# ADE_short.net
KiCad netlist of a schematic drawn in Altium Designer
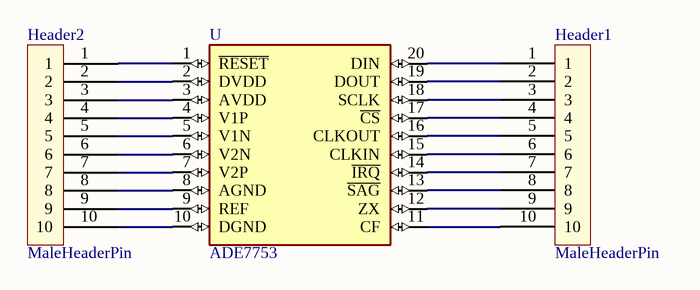
[diagram p0: ADE_short.SchDoc]

(export (version "E")
  (design (tool "Eeschema 10.0.6"))
  (components
    (comp (ref "Header1")
      (value "MaleHeaderPin")
      (footprint "Headerx10")
      (libsource (lib "Schlib1") (part "MaleHeaderPin"))
    )
    (comp (ref "Header2")
      (value "MaleHeaderPin")
      (footprint "Headerx10")
      (libsource (lib "") (part "MaleHeaderPin_1"))
    )
    (comp (ref "U")
      (value "ADE7753")
      (footprint "SSOP-20")
      (description "IC ENERGY METERING 1PHASE 20SSOP")
      (fields (field (name "DIGI-KEY_PART_NUMBER") "ADE7753ARSZRLCT-ND") (field (name "MF") "Analog Devices"))
      (libsource (lib "ADE7753") (part "ADE7753"))
    )
  )
  (nets
    (net (code "1") (name "Net-(U-AGND)") (class "Default")
      (node (ref "Header2") (pin "8") (pinfunction "8_8") (pintype "passive"))
      (node (ref "U") (pin "8") (pinfunction "AGND_8") (pintype "bidirectional"))
    )
    (net (code "2") (name "Net-(U-AVDD)") (class "Default")
      (node (ref "Header2") (pin "3") (pinfunction "3_3") (pintype "passive"))
      (node (ref "U") (pin "3") (pinfunction "AVDD_3") (pintype "bidirectional"))
    )
    (net (code "3") (name "Net-(U-CF)") (class "Default")
      (node (ref "Header1") (pin "10") (pinfunction "10_10") (pintype "passive"))
      (node (ref "U") (pin "11") (pinfunction "CF_11") (pintype "bidirectional"))
    )
    (net (code "4") (name "Net-(U-CLKIN)") (class "Default")
      (node (ref "Header1") (pin "6") (pinfunction "6_6") (pintype "passive"))
      (node (ref "U") (pin "15") (pinfunction "CLKIN_15") (pintype "bidirectional"))
    )
    (net (code "5") (name "Net-(U-CLKOUT)") (class "Default")
      (node (ref "Header1") (pin "5") (pinfunction "5_5") (pintype "passive"))
      (node (ref "U") (pin "16") (pinfunction "CLKOUT_16") (pintype "bidirectional"))
    )
    (net (code "6") (name "Net-(U-DGND)") (class "Default")
      (node (ref "Header2") (pin "10") (pinfunction "10_10") (pintype "passive"))
      (node (ref "U") (pin "10") (pinfunction "DGND_10") (pintype "bidirectional"))
    )
    (net (code "7") (name "Net-(U-DIN)") (class "Default")
      (node (ref "Header1") (pin "1") (pinfunction "1_1") (pintype "passive"))
      (node (ref "U") (pin "20") (pinfunction "DIN_20") (pintype "bidirectional"))
    )
    (net (code "8") (name "Net-(U-DOUT)") (class "Default")
      (node (ref "Header1") (pin "2") (pinfunction "2_2") (pintype "passive"))
      (node (ref "U") (pin "19") (pinfunction "DOUT_19") (pintype "bidirectional"))
    )
    (net (code "9") (name "Net-(U-DVDD)") (class "Default")
      (node (ref "Header2") (pin "2") (pinfunction "2_2") (pintype "passive"))
      (node (ref "U") (pin "2") (pinfunction "DVDD_2") (pintype "bidirectional"))
    )
    (net (code "10") (name "Net-(U-REF)") (class "Default")
      (node (ref "Header2") (pin "9") (pinfunction "9_9") (pintype "passive"))
      (node (ref "U") (pin "9") (pinfunction "REF_9") (pintype "bidirectional"))
    )
    (net (code "11") (name "Net-(U-SCLK)") (class "Default")
      (node (ref "Header1") (pin "3") (pinfunction "3_3") (pintype "passive"))
      (node (ref "U") (pin "18") (pinfunction "SCLK_18") (pintype "bidirectional"))
    )
    (net (code "12") (name "Net-(U-V1N)") (class "Default")
      (node (ref "Header2") (pin "5") (pinfunction "5_5") (pintype "passive"))
      (node (ref "U") (pin "5") (pinfunction "V1N_5") (pintype "bidirectional"))
    )
    (net (code "13") (name "Net-(U-V1P)") (class "Default")
      (node (ref "Header2") (pin "4") (pinfunction "4_4") (pintype "passive"))
      (node (ref "U") (pin "4") (pinfunction "V1P_4") (pintype "bidirectional"))
    )
    (net (code "14") (name "Net-(U-V2N)") (class "Default")
      (node (ref "Header2") (pin "6") (pinfunction "6_6") (pintype "passive"))
      (node (ref "U") (pin "6") (pinfunction "V2N_6") (pintype "bidirectional"))
    )
    (net (code "15") (name "Net-(U-V2P)") (class "Default")
      (node (ref "Header2") (pin "7") (pinfunction "7_7") (pintype "passive"))
      (node (ref "U") (pin "7") (pinfunction "V2P_7") (pintype "bidirectional"))
    )
    (net (code "16") (name "Net-(U-ZX)") (class "Default")
      (node (ref "Header1") (pin "9") (pinfunction "9_9") (pintype "passive"))
      (node (ref "U") (pin "12") (pinfunction "ZX_12") (pintype "bidirectional"))
    )
    (net (code "17") (name "Net-(U-~{CS})") (class "Default")
      (node (ref "Header1") (pin "4") (pinfunction "4_4") (pintype "passive"))
      (node (ref "U") (pin "17") (pinfunction "~{CS}_17") (pintype "bidirectional"))
    )
    (net (code "18") (name "Net-(U-~{IRQ})") (class "Default")
      (node (ref "Header1") (pin "7") (pinfunction "7_7") (pintype "passive"))
      (node (ref "U") (pin "14") (pinfunction "~{IRQ}_14") (pintype "bidirectional"))
    )
    (net (code "19") (name "Net-(U-~{RESET})") (class "Default")
      (node (ref "Header2") (pin "1") (pinfunction "1_1") (pintype "passive"))
      (node (ref "U") (pin "1") (pinfunction "~{RESET}_1") (pintype "bidirectional"))
    )
    (net (code "20") (name "Net-(U-~{SAG})") (class "Default")
      (node (ref "Header1") (pin "8") (pinfunction "8_8") (pintype "passive"))
      (node (ref "U") (pin "13") (pinfunction "~{SAG}_13") (pintype "bidirectional"))
    )
  )
)
